# Cryo_DFFs_SCH.net
KiCad netlist of a schematic drawn in Altium Designer
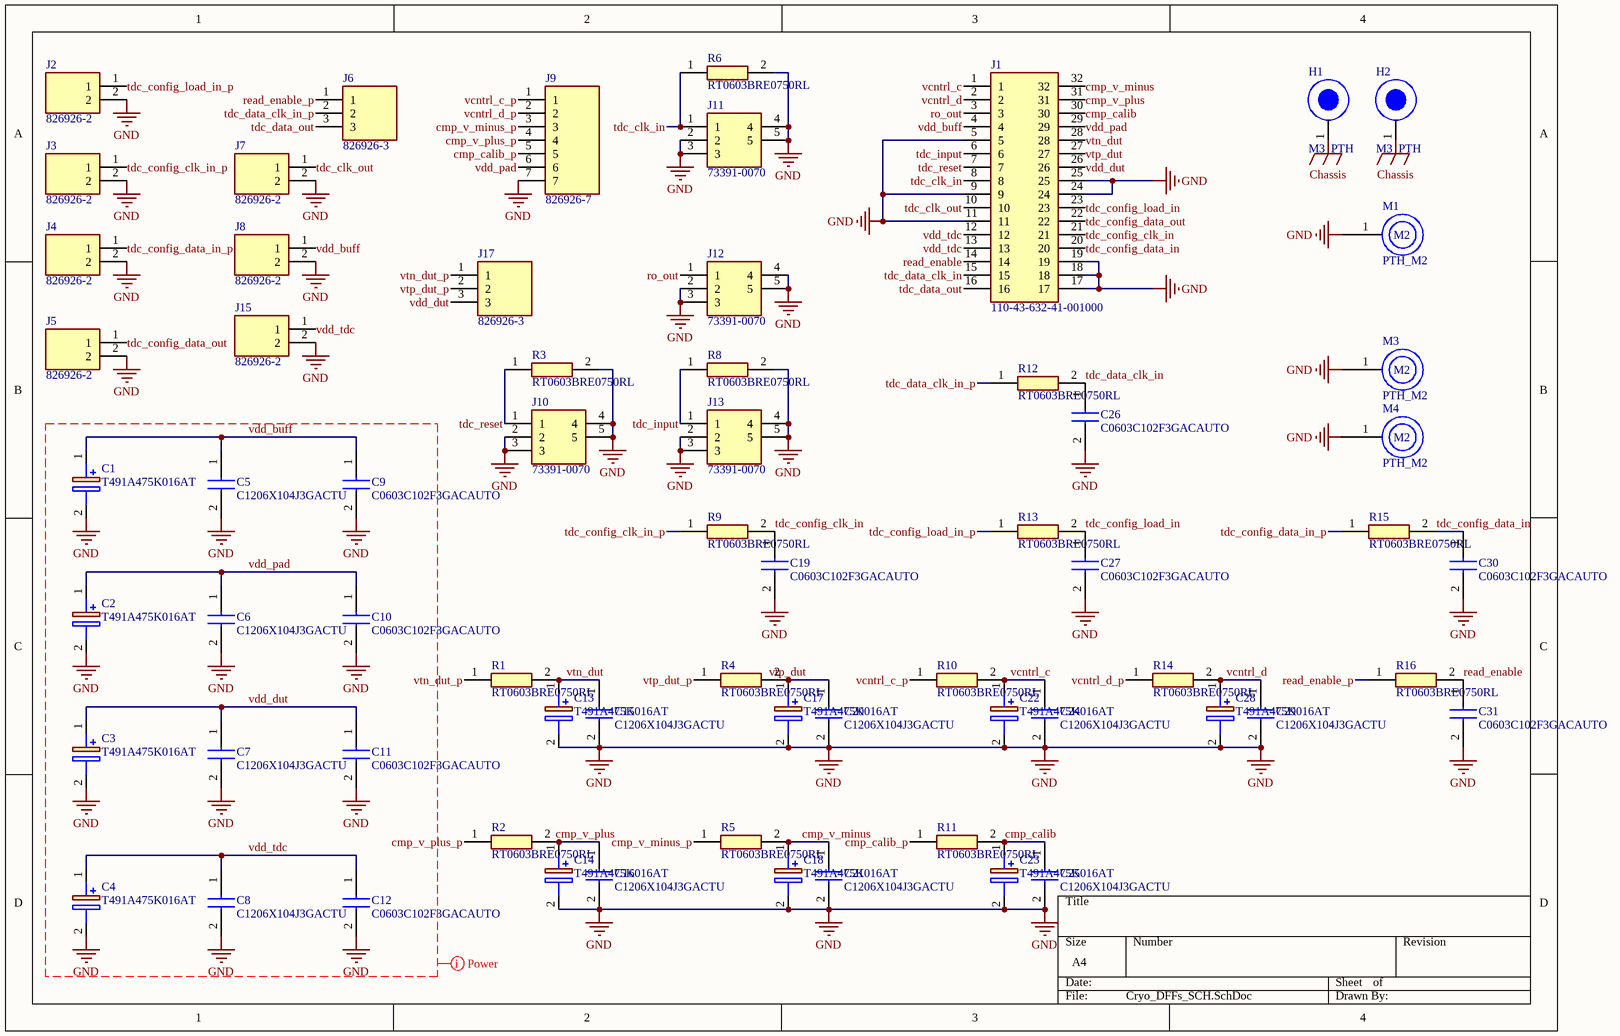
[diagram p0: Cryo_DFFs_SCH.SchDoc]

(export (version "E")
  (design (tool "Eeschema 10.0.6"))
  (components
    (comp (ref "C1")
      (value "T491A475K016AT")
      (footprint "SamacSys:T491A")
      (description "Capacitor Polarised")
      (fields (field (name "MOUSER PART NUMBER") "80-T491A475K016"))
      (libsource (lib "*") (part "T491A475K016AT"))
    )
    (comp (ref "C2")
      (value "T491A475K016AT")
      (footprint "SamacSys:T491A")
      (description "Capacitor Polarised")
      (fields (field (name "MOUSER PART NUMBER") "80-T491A475K016"))
      (libsource (lib "*") (part "T491A475K016AT"))
    )
    (comp (ref "C3")
      (value "T491A475K016AT")
      (footprint "SamacSys:T491A")
      (description "Capacitor Polarised")
      (fields (field (name "MOUSER PART NUMBER") "80-T491A475K016"))
      (libsource (lib "*") (part "T491A475K016AT"))
    )
    (comp (ref "C4")
      (value "T491A475K016AT")
      (footprint "SamacSys:T491A")
      (description "Capacitor Polarised")
      (fields (field (name "MOUSER PART NUMBER") "80-T491A475K016"))
      (libsource (lib "*") (part "T491A475K016AT"))
    )
    (comp (ref "C5")
      (value "C1206X104J3GACTU")
      (footprint "SamacSys:C1206_FT")
      (description "Capacitor")
      (fields (field (name "MOUSER PART NUMBER") "80-C1206X104J3G"))
      (libsource (lib "*") (part "C1206X104J3GACTU"))
    )
    (comp (ref "C6")
      (value "C1206X104J3GACTU")
      (footprint "SamacSys:C1206_FT")
      (description "Capacitor")
      (fields (field (name "MOUSER PART NUMBER") "80-C1206X104J3G"))
      (libsource (lib "*") (part "C1206X104J3GACTU"))
    )
    (comp (ref "C7")
      (value "C1206X104J3GACTU")
      (footprint "SamacSys:C1206_FT")
      (description "Capacitor")
      (fields (field (name "MOUSER PART NUMBER") "80-C1206X104J3G"))
      (libsource (lib "*") (part "C1206X104J3GACTU"))
    )
    (comp (ref "C8")
      (value "C1206X104J3GACTU")
      (footprint "SamacSys:C1206_FT")
      (description "Capacitor")
      (fields (field (name "MOUSER PART NUMBER") "80-C1206X104J3G"))
      (libsource (lib "*") (part "C1206X104J3GACTU"))
    )
    (comp (ref "C9")
      (value "C0603C102F3GACAUTO")
      (footprint "SamacSys:C0603")
      (description "Capacitor")
      (fields (field (name "MOUSER PART NUMBER") "80-C0603C102F3GAUTO"))
      (libsource (lib "*") (part "C0603C102F3GACAUTO"))
    )
    (comp (ref "C10")
      (value "C0603C102F3GACAUTO")
      (footprint "SamacSys:C0603")
      (description "Capacitor")
      (fields (field (name "MOUSER PART NUMBER") "80-C0603C102F3GAUTO"))
      (libsource (lib "*") (part "C0603C102F3GACAUTO"))
    )
    (comp (ref "C11")
      (value "C0603C102F3GACAUTO")
      (footprint "SamacSys:C0603")
      (description "Capacitor")
      (fields (field (name "MOUSER PART NUMBER") "80-C0603C102F3GAUTO"))
      (libsource (lib "*") (part "C0603C102F3GACAUTO"))
    )
    (comp (ref "C12")
      (value "C0603C102F3GACAUTO")
      (footprint "SamacSys:C0603")
      (description "Capacitor")
      (fields (field (name "MOUSER PART NUMBER") "80-C0603C102F3GAUTO"))
      (libsource (lib "*") (part "C0603C102F3GACAUTO"))
    )
    (comp (ref "C13")
      (value "T491A475K016AT")
      (footprint "SamacSys:T491A")
      (description "Capacitor Polarised")
      (fields (field (name "MOUSER PART NUMBER") "80-T491A475K016"))
      (libsource (lib "*") (part "T491A475K016AT"))
    )
    (comp (ref "C14")
      (value "T491A475K016AT")
      (footprint "SamacSys:T491A")
      (description "Capacitor Polarised")
      (fields (field (name "MOUSER PART NUMBER") "80-T491A475K016"))
      (libsource (lib "*") (part "T491A475K016AT"))
    )
    (comp (ref "C15")
      (value "C1206X104J3GACTU")
      (footprint "SamacSys:C1206_FT")
      (description "Capacitor")
      (fields (field (name "MOUSER PART NUMBER") "80-C1206X104J3G"))
      (libsource (lib "*") (part "C1206X104J3GACTU"))
    )
    (comp (ref "C16")
      (value "C1206X104J3GACTU")
      (footprint "SamacSys:C1206_FT")
      (description "Capacitor")
      (fields (field (name "MOUSER PART NUMBER") "80-C1206X104J3G"))
      (libsource (lib "*") (part "C1206X104J3GACTU"))
    )
    (comp (ref "C17")
      (value "T491A475K016AT")
      (footprint "SamacSys:T491A")
      (description "Capacitor Polarised")
      (fields (field (name "MOUSER PART NUMBER") "80-T491A475K016"))
      (libsource (lib "*") (part "T491A475K016AT"))
    )
    (comp (ref "C18")
      (value "T491A475K016AT")
      (footprint "SamacSys:T491A")
      (description "Capacitor Polarised")
      (fields (field (name "MOUSER PART NUMBER") "80-T491A475K016"))
      (libsource (lib "*") (part "T491A475K016AT"))
    )
    (comp (ref "C19")
      (value "C0603C102F3GACAUTO")
      (footprint "SamacSys:C0603")
      (description "Capacitor")
      (fields (field (name "MOUSER PART NUMBER") "80-C0603C102F3GAUTO"))
      (libsource (lib "*") (part "C0603C102F3GACAUTO"))
    )
    (comp (ref "C20")
      (value "C1206X104J3GACTU")
      (footprint "SamacSys:C1206_FT")
      (description "Capacitor")
      (fields (field (name "MOUSER PART NUMBER") "80-C1206X104J3G"))
      (libsource (lib "*") (part "C1206X104J3GACTU"))
    )
    (comp (ref "C21")
      (value "C1206X104J3GACTU")
      (footprint "SamacSys:C1206_FT")
      (description "Capacitor")
      (fields (field (name "MOUSER PART NUMBER") "80-C1206X104J3G"))
      (libsource (lib "*") (part "C1206X104J3GACTU"))
    )
    (comp (ref "C22")
      (value "T491A475K016AT")
      (footprint "SamacSys:T491A")
      (description "Capacitor Polarised")
      (fields (field (name "MOUSER PART NUMBER") "80-T491A475K016"))
      (libsource (lib "*") (part "T491A475K016AT"))
    )
    (comp (ref "C23")
      (value "T491A475K016AT")
      (footprint "SamacSys:T491A")
      (description "Capacitor Polarised")
      (fields (field (name "MOUSER PART NUMBER") "80-T491A475K016"))
      (libsource (lib "*") (part "T491A475K016AT"))
    )
    (comp (ref "C24")
      (value "C1206X104J3GACTU")
      (footprint "SamacSys:C1206_FT")
      (description "Capacitor")
      (fields (field (name "MOUSER PART NUMBER") "80-C1206X104J3G"))
      (libsource (lib "*") (part "C1206X104J3GACTU"))
    )
    (comp (ref "C25")
      (value "C1206X104J3GACTU")
      (footprint "SamacSys:C1206_FT")
      (description "Capacitor")
      (fields (field (name "MOUSER PART NUMBER") "80-C1206X104J3G"))
      (libsource (lib "*") (part "C1206X104J3GACTU"))
    )
    (comp (ref "C26")
      (value "C0603C102F3GACAUTO")
      (footprint "SamacSys:C0603")
      (description "Capacitor")
      (fields (field (name "MOUSER PART NUMBER") "80-C0603C102F3GAUTO"))
      (libsource (lib "*") (part "C0603C102F3GACAUTO"))
    )
    (comp (ref "C27")
      (value "C0603C102F3GACAUTO")
      (footprint "SamacSys:C0603")
      (description "Capacitor")
      (fields (field (name "MOUSER PART NUMBER") "80-C0603C102F3GAUTO"))
      (libsource (lib "*") (part "C0603C102F3GACAUTO"))
    )
    (comp (ref "C28")
      (value "T491A475K016AT")
      (footprint "SamacSys:T491A")
      (description "Capacitor Polarised")
      (fields (field (name "MOUSER PART NUMBER") "80-T491A475K016"))
      (libsource (lib "*") (part "T491A475K016AT"))
    )
    (comp (ref "C29")
      (value "C1206X104J3GACTU")
      (footprint "SamacSys:C1206_FT")
      (description "Capacitor")
      (fields (field (name "MOUSER PART NUMBER") "80-C1206X104J3G"))
      (libsource (lib "*") (part "C1206X104J3GACTU"))
    )
    (comp (ref "C30")
      (value "C0603C102F3GACAUTO")
      (footprint "SamacSys:C0603")
      (description "Capacitor")
      (fields (field (name "MOUSER PART NUMBER") "80-C0603C102F3GAUTO"))
      (libsource (lib "*") (part "C0603C102F3GACAUTO"))
    )
    (comp (ref "C31")
      (value "C0603C102F3GACAUTO")
      (footprint "SamacSys:C0603")
      (description "Capacitor")
      (fields (field (name "MOUSER PART NUMBER") "80-C0603C102F3GAUTO"))
      (libsource (lib "*") (part "C0603C102F3GACAUTO"))
    )
    (comp (ref "H1")
      (value "M3_PTH")
      (footprint "M3_PTH")
      (description "Plated M3 hole")
      (libsource (lib "Custom_Conn") (part "M3_PTH"))
    )
    (comp (ref "H2")
      (value "M3_PTH")
      (footprint "M3_PTH")
      (description "Plated M3 hole")
      (libsource (lib "Custom_Conn") (part "M3_PTH"))
    )
    (comp (ref "J1")
      (value "110-43-632-41-001000")
      (footprint "DIPS1524W51P254L4064H419Q32N")
      (description "Connector")
      (fields (field (name "MOUSER PART NUMBER") "575-11043632"))
      (libsource (lib "*") (part "110-43-632-41-001000"))
    )
    (comp (ref "J2")
      (value "826926-2")
      (footprint "SamacSys:HDRV2W63P0X254_1X2_508X250X970P")
      (description "Connector")
      (fields (field (name "MOUSER PART NUMBER") "571-826926-2"))
      (libsource (lib "*") (part "826926-2"))
    )
    (comp (ref "J3")
      (value "826926-2")
      (footprint "SamacSys:HDRV2W63P0X254_1X2_508X250X970P")
      (description "Connector")
      (fields (field (name "MOUSER PART NUMBER") "571-826926-2"))
      (libsource (lib "*") (part "826926-2"))
    )
    (comp (ref "J4")
      (value "826926-2")
      (footprint "SamacSys:HDRV2W63P0X254_1X2_508X250X970P")
      (description "Connector")
      (fields (field (name "MOUSER PART NUMBER") "571-826926-2"))
      (libsource (lib "*") (part "826926-2"))
    )
    (comp (ref "J5")
      (value "826926-2")
      (footprint "SamacSys:HDRV2W63P0X254_1X2_508X250X970P")
      (description "Connector")
      (fields (field (name "MOUSER PART NUMBER") "571-826926-2"))
      (libsource (lib "*") (part "826926-2"))
    )
    (comp (ref "J6")
      (value "826926-3")
      (footprint "SamacSys:HDRV3W63P0X254_1X3_762X250X950P")
      (description "Connector")
      (fields (field (name "MOUSER PART NUMBER") "571-826926-3"))
      (libsource (lib "*") (part "826926-3"))
    )
    (comp (ref "J7")
      (value "826926-2")
      (footprint "SamacSys:HDRV2W63P0X254_1X2_508X250X970P")
      (description "Connector")
      (fields (field (name "MOUSER PART NUMBER") "571-826926-2"))
      (libsource (lib "*") (part "826926-2"))
    )
    (comp (ref "J8")
      (value "826926-2")
      (footprint "SamacSys:HDRV2W63P0X254_1X2_508X250X970P")
      (description "Connector")
      (fields (field (name "MOUSER PART NUMBER") "571-826926-2"))
      (libsource (lib "*") (part "826926-2"))
    )
    (comp (ref "J9")
      (value "826926-7")
      (footprint "HDRV7W63P0X254_1X7_1778X250X970P")
      (description "Connector")
      (fields (field (name "MOUSER PART NUMBER") "571-826926-7"))
      (libsource (lib "*") (part "826926-7"))
    )
    (comp (ref "J10")
      (value "73391-0070")
      (footprint "SamacSys:733910070")
      (description "Connector")
      (fields (field (name "MOUSER PART NUMBER") "538-73391-0070"))
      (libsource (lib "*") (part "73391-0070"))
    )
    (comp (ref "J11")
      (value "73391-0070")
      (footprint "SamacSys:733910070")
      (description "Connector")
      (fields (field (name "MOUSER PART NUMBER") "538-73391-0070"))
      (libsource (lib "*") (part "73391-0070"))
    )
    (comp (ref "J12")
      (value "73391-0070")
      (footprint "SamacSys:733910070")
      (description "Connector")
      (fields (field (name "MOUSER PART NUMBER") "538-73391-0070"))
      (libsource (lib "*") (part "73391-0070"))
    )
    (comp (ref "J13")
      (value "73391-0070")
      (footprint "SamacSys:733910070")
      (description "Connector")
      (fields (field (name "MOUSER PART NUMBER") "538-73391-0070"))
      (libsource (lib "*") (part "73391-0070"))
    )
    (comp (ref "J15")
      (value "826926-2")
      (footprint "SamacSys:HDRV2W63P0X254_1X2_508X250X970P")
      (description "Connector")
      (fields (field (name "MOUSER PART NUMBER") "571-826926-2"))
      (libsource (lib "*") (part "826926-2"))
    )
    (comp (ref "J17")
      (value "826926-3")
      (footprint "SamacSys:HDRV3W63P0X254_1X3_762X250X950P")
      (description "Connector")
      (fields (field (name "MOUSER PART NUMBER") "571-826926-3"))
      (libsource (lib "*") (part "826926-3"))
    )
    (comp (ref "M1")
      (value "PTH_M2")
      (footprint "PTH_M2")
      (description "PTH")
      (libsource (lib "SamacSys") (part "PTH_M2"))
    )
    (comp (ref "M3")
      (value "PTH_M2")
      (footprint "PTH_M2")
      (description "PTH")
      (libsource (lib "SamacSys") (part "PTH_M2"))
    )
    (comp (ref "M4")
      (value "PTH_M2")
      (footprint "PTH_M2")
      (description "PTH")
      (libsource (lib "SamacSys") (part "PTH_M2"))
    )
    (comp (ref "R1")
      (value "RT0603BRE0750RL")
      (footprint "SamacSys:RESC1608X55N")
      (description "Resistor")
      (fields (field (name "MOUSER PART NUMBER") "603-RT0603BRE0750RL"))
      (libsource (lib "*") (part "RT0603BRE0750RL"))
    )
    (comp (ref "R2")
      (value "RT0603BRE0750RL")
      (footprint "SamacSys:RESC1608X55N")
      (description "Resistor")
      (fields (field (name "MOUSER PART NUMBER") "603-RT0603BRE0750RL"))
      (libsource (lib "*") (part "RT0603BRE0750RL"))
    )
    (comp (ref "R3")
      (value "RT0603BRE0750RL")
      (footprint "SamacSys:RESC1608X55N")
      (description "Resistor")
      (fields (field (name "MOUSER PART NUMBER") "603-RT0603BRE0750RL"))
      (libsource (lib "*") (part "RT0603BRE0750RL"))
    )
    (comp (ref "R4")
      (value "RT0603BRE0750RL")
      (footprint "SamacSys:RESC1608X55N")
      (description "Resistor")
      (fields (field (name "MOUSER PART NUMBER") "603-RT0603BRE0750RL"))
      (libsource (lib "*") (part "RT0603BRE0750RL"))
    )
    (comp (ref "R5")
      (value "RT0603BRE0750RL")
      (footprint "SamacSys:RESC1608X55N")
      (description "Resistor")
      (fields (field (name "MOUSER PART NUMBER") "603-RT0603BRE0750RL"))
      (libsource (lib "*") (part "RT0603BRE0750RL"))
    )
    (comp (ref "R6")
      (value "RT0603BRE0750RL")
      (footprint "SamacSys:RESC1608X55N")
      (description "Resistor")
      (fields (field (name "MOUSER PART NUMBER") "603-RT0603BRE0750RL"))
      (libsource (lib "*") (part "RT0603BRE0750RL"))
    )
    (comp (ref "R8")
      (value "RT0603BRE0750RL")
      (footprint "SamacSys:RESC1608X55N")
      (description "Resistor")
      (fields (field (name "MOUSER PART NUMBER") "603-RT0603BRE0750RL"))
      (libsource (lib "*") (part "RT0603BRE0750RL"))
    )
    (comp (ref "R9")
      (value "RT0603BRE0750RL")
      (footprint "SamacSys:RESC1608X55N")
      (description "Resistor")
      (fields (field (name "MOUSER PART NUMBER") "603-RT0603BRE0750RL"))
      (libsource (lib "*") (part "RT0603BRE0750RL"))
    )
    (comp (ref "R10")
      (value "RT0603BRE0750RL")
      (footprint "SamacSys:RESC1608X55N")
      (description "Resistor")
      (fields (field (name "MOUSER PART NUMBER") "603-RT0603BRE0750RL"))
      (libsource (lib "*") (part "RT0603BRE0750RL"))
    )
    (comp (ref "R11")
      (value "RT0603BRE0750RL")
      (footprint "SamacSys:RESC1608X55N")
      (description "Resistor")
      (fields (field (name "MOUSER PART NUMBER") "603-RT0603BRE0750RL"))
      (libsource (lib "*") (part "RT0603BRE0750RL"))
    )
    (comp (ref "R12")
      (value "RT0603BRE0750RL")
      (footprint "SamacSys:RESC1608X55N")
      (description "Resistor")
      (fields (field (name "MOUSER PART NUMBER") "603-RT0603BRE0750RL"))
      (libsource (lib "*") (part "RT0603BRE0750RL"))
    )
    (comp (ref "R13")
      (value "RT0603BRE0750RL")
      (footprint "SamacSys:RESC1608X55N")
      (description "Resistor")
      (fields (field (name "MOUSER PART NUMBER") "603-RT0603BRE0750RL"))
      (libsource (lib "*") (part "RT0603BRE0750RL"))
    )
    (comp (ref "R14")
      (value "RT0603BRE0750RL")
      (footprint "SamacSys:RESC1608X55N")
      (description "Resistor")
      (fields (field (name "MOUSER PART NUMBER") "603-RT0603BRE0750RL"))
      (libsource (lib "*") (part "RT0603BRE0750RL"))
    )
    (comp (ref "R15")
      (value "RT0603BRE0750RL")
      (footprint "SamacSys:RESC1608X55N")
      (description "Resistor")
      (fields (field (name "MOUSER PART NUMBER") "603-RT0603BRE0750RL"))
      (libsource (lib "*") (part "RT0603BRE0750RL"))
    )
    (comp (ref "R16")
      (value "RT0603BRE0750RL")
      (footprint "SamacSys:RESC1608X55N")
      (description "Resistor")
      (fields (field (name "MOUSER PART NUMBER") "603-RT0603BRE0750RL"))
      (libsource (lib "*") (part "RT0603BRE0750RL"))
    )
  )
  (nets
    (net (code "1") (name "/cmp_calib") (class "Default")
      (node (ref "C23") (pin "1") (pinfunction "+_1") (pintype "passive"))
      (node (ref "C25") (pin "1") (pinfunction "1_1") (pintype "passive"))
      (node (ref "J1") (pin "30") (pinfunction "30_30") (pintype "passive"))
      (node (ref "R11") (pin "2") (pinfunction "2_2") (pintype "passive"))
    )
    (net (code "2") (name "/cmp_calib_p") (class "Default")
      (node (ref "J9") (pin "5") (pinfunction "5_5") (pintype "passive"))
      (node (ref "R11") (pin "1") (pinfunction "1_1") (pintype "passive"))
    )
    (net (code "3") (name "/cmp_v_minus") (class "Default")
      (node (ref "C18") (pin "1") (pinfunction "+_1") (pintype "passive"))
      (node (ref "C21") (pin "1") (pinfunction "1_1") (pintype "passive"))
      (node (ref "J1") (pin "32") (pinfunction "32_32") (pintype "passive"))
      (node (ref "R5") (pin "2") (pinfunction "2_2") (pintype "passive"))
    )
    (net (code "4") (name "/cmp_v_minus_p") (class "Default")
      (node (ref "J9") (pin "3") (pinfunction "3_3") (pintype "passive"))
      (node (ref "R5") (pin "1") (pinfunction "1_1") (pintype "passive"))
    )
    (net (code "5") (name "/cmp_v_plus") (class "Default")
      (node (ref "C14") (pin "1") (pinfunction "+_1") (pintype "passive"))
      (node (ref "C16") (pin "1") (pinfunction "1_1") (pintype "passive"))
      (node (ref "J1") (pin "31") (pinfunction "31_31") (pintype "passive"))
      (node (ref "R2") (pin "2") (pinfunction "2_2") (pintype "passive"))
    )
    (net (code "6") (name "/cmp_v_plus_p") (class "Default")
      (node (ref "J9") (pin "4") (pinfunction "4_4") (pintype "passive"))
      (node (ref "R2") (pin "1") (pinfunction "1_1") (pintype "passive"))
    )
    (net (code "7") (name "/read_enable") (class "Default")
      (node (ref "C31") (pin "1") (pinfunction "1_1") (pintype "passive"))
      (node (ref "J1") (pin "14") (pinfunction "14_14") (pintype "passive"))
      (node (ref "R16") (pin "2") (pinfunction "2_2") (pintype "passive"))
    )
    (net (code "8") (name "/read_enable_p") (class "Default")
      (node (ref "J6") (pin "1") (pinfunction "1_1") (pintype "passive"))
      (node (ref "R16") (pin "1") (pinfunction "1_1") (pintype "passive"))
    )
    (net (code "9") (name "/ro_out") (class "Default")
      (node (ref "J1") (pin "3") (pinfunction "3_3") (pintype "passive"))
      (node (ref "J12") (pin "1") (pinfunction "1_1") (pintype "passive"))
    )
    (net (code "10") (name "/tdc_clk_in") (class "Default")
      (node (ref "J1") (pin "8") (pinfunction "8_8") (pintype "passive"))
      (node (ref "J11") (pin "1") (pinfunction "1_1") (pintype "passive"))
      (node (ref "R6") (pin "1") (pinfunction "1_1") (pintype "passive"))
    )
    (net (code "11") (name "/tdc_clk_out") (class "Default")
      (node (ref "J1") (pin "10") (pinfunction "10_10") (pintype "passive"))
      (node (ref "J7") (pin "1") (pinfunction "1_1") (pintype "passive"))
    )
    (net (code "12") (name "/tdc_config_clk_in") (class "Default")
      (node (ref "C19") (pin "1") (pinfunction "1_1") (pintype "passive"))
      (node (ref "J1") (pin "21") (pinfunction "21_21") (pintype "passive"))
      (node (ref "R9") (pin "2") (pinfunction "2_2") (pintype "passive"))
    )
    (net (code "13") (name "/tdc_config_clk_in_p") (class "Default")
      (node (ref "J3") (pin "1") (pinfunction "1_1") (pintype "passive"))
      (node (ref "R9") (pin "1") (pinfunction "1_1") (pintype "passive"))
    )
    (net (code "14") (name "/tdc_config_data_in") (class "Default")
      (node (ref "C30") (pin "1") (pinfunction "1_1") (pintype "passive"))
      (node (ref "J1") (pin "20") (pinfunction "20_20") (pintype "passive"))
      (node (ref "R15") (pin "2") (pinfunction "2_2") (pintype "passive"))
    )
    (net (code "15") (name "/tdc_config_data_in_p") (class "Default")
      (node (ref "J4") (pin "1") (pinfunction "1_1") (pintype "passive"))
      (node (ref "R15") (pin "1") (pinfunction "1_1") (pintype "passive"))
    )
    (net (code "16") (name "/tdc_config_data_out") (class "Default")
      (node (ref "J1") (pin "22") (pinfunction "22_22") (pintype "passive"))
      (node (ref "J5") (pin "1") (pinfunction "1_1") (pintype "passive"))
    )
    (net (code "17") (name "/tdc_config_load_in") (class "Default")
      (node (ref "C27") (pin "1") (pinfunction "1_1") (pintype "passive"))
      (node (ref "J1") (pin "23") (pinfunction "23_23") (pintype "passive"))
      (node (ref "R13") (pin "2") (pinfunction "2_2") (pintype "passive"))
    )
    (net (code "18") (name "/tdc_config_load_in_p") (class "Default")
      (node (ref "J2") (pin "1") (pinfunction "1_1") (pintype "passive"))
      (node (ref "R13") (pin "1") (pinfunction "1_1") (pintype "passive"))
    )
    (net (code "19") (name "/tdc_data_clk_in") (class "Default")
      (node (ref "C26") (pin "1") (pinfunction "1_1") (pintype "passive"))
      (node (ref "J1") (pin "15") (pinfunction "15_15") (pintype "passive"))
      (node (ref "R12") (pin "2") (pinfunction "2_2") (pintype "passive"))
    )
    (net (code "20") (name "/tdc_data_clk_in_p") (class "Default")
      (node (ref "J6") (pin "2") (pinfunction "2_2") (pintype "passive"))
      (node (ref "R12") (pin "1") (pinfunction "1_1") (pintype "passive"))
    )
    (net (code "21") (name "/tdc_data_out") (class "Default")
      (node (ref "J1") (pin "16") (pinfunction "16_16") (pintype "passive"))
      (node (ref "J6") (pin "3") (pinfunction "3_3") (pintype "passive"))
    )
    (net (code "22") (name "/tdc_input") (class "Default")
      (node (ref "J1") (pin "6") (pinfunction "6_6") (pintype "passive"))
      (node (ref "J13") (pin "1") (pinfunction "1_1") (pintype "passive"))
      (node (ref "R8") (pin "1") (pinfunction "1_1") (pintype "passive"))
    )
    (net (code "23") (name "/tdc_reset") (class "Default")
      (node (ref "J1") (pin "7") (pinfunction "7_7") (pintype "passive"))
      (node (ref "J10") (pin "1") (pinfunction "1_1") (pintype "passive"))
      (node (ref "R3") (pin "1") (pinfunction "1_1") (pintype "passive"))
    )
    (net (code "24") (name "/vcntrl_c") (class "Default")
      (node (ref "C22") (pin "1") (pinfunction "+_1") (pintype "passive"))
      (node (ref "C24") (pin "1") (pinfunction "1_1") (pintype "passive"))
      (node (ref "J1") (pin "1") (pinfunction "1_1") (pintype "passive"))
      (node (ref "R10") (pin "2") (pinfunction "2_2") (pintype "passive"))
    )
    (net (code "25") (name "/vcntrl_c_p") (class "Default")
      (node (ref "J9") (pin "1") (pinfunction "1_1") (pintype "passive"))
      (node (ref "R10") (pin "1") (pinfunction "1_1") (pintype "passive"))
    )
    (net (code "26") (name "/vcntrl_d") (class "Default")
      (node (ref "C28") (pin "1") (pinfunction "+_1") (pintype "passive"))
      (node (ref "C29") (pin "1") (pinfunction "1_1") (pintype "passive"))
      (node (ref "J1") (pin "2") (pinfunction "2_2") (pintype "passive"))
      (node (ref "R14") (pin "2") (pinfunction "2_2") (pintype "passive"))
    )
    (net (code "27") (name "/vcntrl_d_p") (class "Default")
      (node (ref "J9") (pin "2") (pinfunction "2_2") (pintype "passive"))
      (node (ref "R14") (pin "1") (pinfunction "1_1") (pintype "passive"))
    )
    (net (code "28") (name "/vdd_buff") (class "Default")
      (node (ref "C1") (pin "1") (pinfunction "+_1") (pintype "passive"))
      (node (ref "C5") (pin "1") (pinfunction "1_1") (pintype "passive"))
      (node (ref "C9") (pin "1") (pinfunction "1_1") (pintype "passive"))
      (node (ref "J1") (pin "4") (pinfunction "4_4") (pintype "passive"))
      (node (ref "J8") (pin "1") (pinfunction "1_1") (pintype "passive"))
    )
    (net (code "29") (name "/vdd_dut") (class "Default")
      (node (ref "C11") (pin "1") (pinfunction "1_1") (pintype "passive"))
      (node (ref "C3") (pin "1") (pinfunction "+_1") (pintype "passive"))
      (node (ref "C7") (pin "1") (pinfunction "1_1") (pintype "passive"))
      (node (ref "J1") (pin "26") (pinfunction "26_26") (pintype "passive"))
      (node (ref "J17") (pin "3") (pinfunction "3_3") (pintype "passive"))
    )
    (net (code "30") (name "/vdd_pad") (class "Default")
      (node (ref "C10") (pin "1") (pinfunction "1_1") (pintype "passive"))
      (node (ref "C2") (pin "1") (pinfunction "+_1") (pintype "passive"))
      (node (ref "C6") (pin "1") (pinfunction "1_1") (pintype "passive"))
      (node (ref "J1") (pin "29") (pinfunction "29_29") (pintype "passive"))
      (node (ref "J9") (pin "6") (pinfunction "6_6") (pintype "passive"))
    )
    (net (code "31") (name "/vdd_tdc") (class "Default")
      (node (ref "C12") (pin "1") (pinfunction "1_1") (pintype "passive"))
      (node (ref "C4") (pin "1") (pinfunction "+_1") (pintype "passive"))
      (node (ref "C8") (pin "1") (pinfunction "1_1") (pintype "passive"))
      (node (ref "J1") (pin "12") (pinfunction "12_12") (pintype "passive"))
      (node (ref "J1") (pin "13") (pinfunction "13_13") (pintype "passive"))
      (node (ref "J15") (pin "1") (pinfunction "1_1") (pintype "passive"))
    )
    (net (code "32") (name "/vtn_dut") (class "Default")
      (node (ref "C13") (pin "1") (pinfunction "+_1") (pintype "passive"))
      (node (ref "C15") (pin "1") (pinfunction "1_1") (pintype "passive"))
      (node (ref "J1") (pin "28") (pinfunction "28_28") (pintype "passive"))
      (node (ref "R1") (pin "2") (pinfunction "2_2") (pintype "passive"))
    )
    (net (code "33") (name "/vtn_dut_p") (class "Default")
      (node (ref "J17") (pin "1") (pinfunction "1_1") (pintype "passive"))
      (node (ref "R1") (pin "1") (pinfunction "1_1") (pintype "passive"))
    )
    (net (code "34") (name "/vtp_dut") (class "Default")
      (node (ref "C17") (pin "1") (pinfunction "+_1") (pintype "passive"))
      (node (ref "C20") (pin "1") (pinfunction "1_1") (pintype "passive"))
      (node (ref "J1") (pin "27") (pinfunction "27_27") (pintype "passive"))
      (node (ref "R4") (pin "2") (pinfunction "2_2") (pintype "passive"))
    )
    (net (code "35") (name "/vtp_dut_p") (class "Default")
      (node (ref "J17") (pin "2") (pinfunction "2_2") (pintype "passive"))
      (node (ref "R4") (pin "1") (pinfunction "1_1") (pintype "passive"))
    )
    (net (code "36") (name "Chassis") (class "Default")
      (node (ref "H1") (pin "1") (pintype "passive"))
      (node (ref "H2") (pin "1") (pintype "passive"))
    )
    (net (code "37") (name "GND") (class "Default")
      (node (ref "C1") (pin "2") (pinfunction "-_2") (pintype "passive"))
      (node (ref "C10") (pin "2") (pinfunction "2_2") (pintype "passive"))
      (node (ref "C11") (pin "2") (pinfunction "2_2") (pintype "passive"))
      (node (ref "C12") (pin "2") (pinfunction "2_2") (pintype "passive"))
      (node (ref "C13") (pin "2") (pinfunction "-_2") (pintype "passive"))
      (node (ref "C14") (pin "2") (pinfunction "-_2") (pintype "passive"))
      (node (ref "C15") (pin "2") (pinfunction "2_2") (pintype "passive"))
      (node (ref "C16") (pin "2") (pinfunction "2_2") (pintype "passive"))
      (node (ref "C17") (pin "2") (pinfunction "-_2") (pintype "passive"))
      (node (ref "C18") (pin "2") (pinfunction "-_2") (pintype "passive"))
      (node (ref "C19") (pin "2") (pinfunction "2_2") (pintype "passive"))
      (node (ref "C2") (pin "2") (pinfunction "-_2") (pintype "passive"))
      (node (ref "C20") (pin "2") (pinfunction "2_2") (pintype "passive"))
      (node (ref "C21") (pin "2") (pinfunction "2_2") (pintype "passive"))
      (node (ref "C22") (pin "2") (pinfunction "-_2") (pintype "passive"))
      (node (ref "C23") (pin "2") (pinfunction "-_2") (pintype "passive"))
      (node (ref "C24") (pin "2") (pinfunction "2_2") (pintype "passive"))
      (node (ref "C25") (pin "2") (pinfunction "2_2") (pintype "passive"))
      (node (ref "C26") (pin "2") (pinfunction "2_2") (pintype "passive"))
      (node (ref "C27") (pin "2") (pinfunction "2_2") (pintype "passive"))
      (node (ref "C28") (pin "2") (pinfunction "-_2") (pintype "passive"))
      (node (ref "C29") (pin "2") (pinfunction "2_2") (pintype "passive"))
      (node (ref "C3") (pin "2") (pinfunction "-_2") (pintype "passive"))
      (node (ref "C30") (pin "2") (pinfunction "2_2") (pintype "passive"))
      (node (ref "C31") (pin "2") (pinfunction "2_2") (pintype "passive"))
      (node (ref "C4") (pin "2") (pinfunction "-_2") (pintype "passive"))
      (node (ref "C5") (pin "2") (pinfunction "2_2") (pintype "passive"))
      (node (ref "C6") (pin "2") (pinfunction "2_2") (pintype "passive"))
      (node (ref "C7") (pin "2") (pinfunction "2_2") (pintype "passive"))
      (node (ref "C8") (pin "2") (pinfunction "2_2") (pintype "passive"))
      (node (ref "C9") (pin "2") (pinfunction "2_2") (pintype "passive"))
      (node (ref "J1") (pin "11") (pinfunction "11_11") (pintype "passive"))
      (node (ref "J1") (pin "17") (pinfunction "17_17") (pintype "passive"))
      (node (ref "J1") (pin "18") (pinfunction "18_18") (pintype "passive"))
      (node (ref "J1") (pin "19") (pinfunction "19_19") (pintype "passive"))
      (node (ref "J1") (pin "24") (pinfunction "24_24") (pintype "passive"))
      (node (ref "J1") (pin "25") (pinfunction "25_25") (pintype "passive"))
      (node (ref "J1") (pin "5") (pinfunction "5_5") (pintype "passive"))
      (node (ref "J1") (pin "9") (pinfunction "9_9") (pintype "passive"))
      (node (ref "J10") (pin "2") (pinfunction "2_2") (pintype "passive"))
      (node (ref "J10") (pin "3") (pinfunction "3_3") (pintype "passive"))
      (node (ref "J10") (pin "4") (pinfunction "4_4") (pintype "passive"))
      (node (ref "J10") (pin "5") (pinfunction "5_5") (pintype "passive"))
      (node (ref "J11") (pin "2") (pinfunction "2_2") (pintype "passive"))
      (node (ref "J11") (pin "3") (pinfunction "3_3") (pintype "passive"))
      (node (ref "J11") (pin "4") (pinfunction "4_4") (pintype "passive"))
      (node (ref "J11") (pin "5") (pinfunction "5_5") (pintype "passive"))
      (node (ref "J12") (pin "2") (pinfunction "2_2") (pintype "passive"))
      (node (ref "J12") (pin "3") (pinfunction "3_3") (pintype "passive"))
      (node (ref "J12") (pin "4") (pinfunction "4_4") (pintype "passive"))
      (node (ref "J12") (pin "5") (pinfunction "5_5") (pintype "passive"))
      (node (ref "J13") (pin "2") (pinfunction "2_2") (pintype "passive"))
      (node (ref "J13") (pin "3") (pinfunction "3_3") (pintype "passive"))
      (node (ref "J13") (pin "4") (pinfunction "4_4") (pintype "passive"))
      (node (ref "J13") (pin "5") (pinfunction "5_5") (pintype "passive"))
      (node (ref "J15") (pin "2") (pinfunction "2_2") (pintype "passive"))
      (node (ref "J2") (pin "2") (pinfunction "2_2") (pintype "passive"))
      (node (ref "J3") (pin "2") (pinfunction "2_2") (pintype "passive"))
      (node (ref "J4") (pin "2") (pinfunction "2_2") (pintype "passive"))
      (node (ref "J5") (pin "2") (pinfunction "2_2") (pintype "passive"))
      (node (ref "J7") (pin "2") (pinfunction "2_2") (pintype "passive"))
      (node (ref "J8") (pin "2") (pinfunction "2_2") (pintype "passive"))
      (node (ref "J9") (pin "7") (pinfunction "7_7") (pintype "passive"))
      (node (ref "M1") (pin "1") (pintype "passive"))
      (node (ref "M3") (pin "1") (pintype "passive"))
      (node (ref "M4") (pin "1") (pintype "passive"))
      (node (ref "R3") (pin "2") (pinfunction "2_2") (pintype "passive"))
      (node (ref "R6") (pin "2") (pinfunction "2_2") (pintype "passive"))
      (node (ref "R8") (pin "2") (pinfunction "2_2") (pintype "passive"))
    )
  )
)
